# lcd.net
KiCad netlist of a schematic drawn in EAGLE
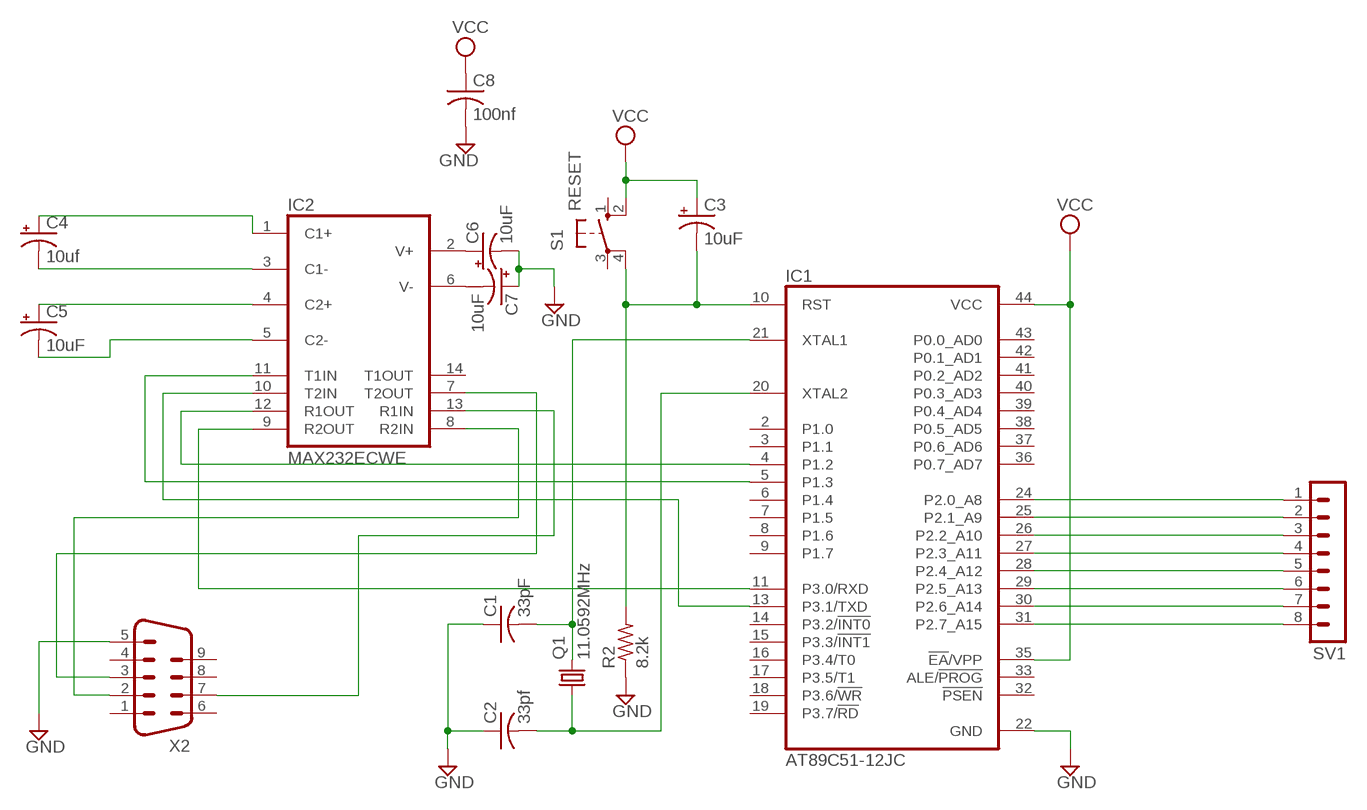
[diagram p0: schematic, sheet 1]

(export (version "E")
  (design (tool "Eeschema 10.0.6"))
  (components
    (comp (ref "C1")
      (value "33pF")
      (footprint "eagle-import:C025-025X050")
      (libsource (lib "eagle-import") (part "C-US025-025X050"))
    )
    (comp (ref "C2")
      (value "33pf")
      (footprint "eagle-import:C025-025X050")
      (libsource (lib "eagle-import") (part "C-US025-025X050"))
    )
    (comp (ref "C3")
      (value "10uF")
      (footprint "eagle-import:E2,5-5")
      (libsource (lib "eagle-import") (part "CPOL-USE2.5-5"))
    )
    (comp (ref "C4")
      (value "10uf")
      (footprint "eagle-import:E2,5-5")
      (libsource (lib "eagle-import") (part "CPOL-USE2.5-5"))
    )
    (comp (ref "C5")
      (value "10uF")
      (footprint "eagle-import:E2,5-5")
      (libsource (lib "eagle-import") (part "CPOL-USE2.5-5"))
    )
    (comp (ref "C6")
      (value "10uF")
      (footprint "eagle-import:E2,5-5")
      (libsource (lib "eagle-import") (part "CPOL-USE2.5-5"))
    )
    (comp (ref "C7")
      (value "10uF")
      (footprint "eagle-import:E2,5-5")
      (libsource (lib "eagle-import") (part "CPOL-USE2.5-5"))
    )
    (comp (ref "C8")
      (value "100nf")
      (footprint "eagle-import:C025-025X050")
      (libsource (lib "eagle-import") (part "C-US025-025X050"))
    )
    (comp (ref "IC1")
      (value "AT89C51-12JC")
      (footprint "eagle-import:PLCC44")
      (fields (field (name "MPN") "AT89C51ED2-SLSUM"))
      (libsource (lib "eagle-import") (part "AT89C51-JC12"))
    )
    (comp (ref "IC2")
      (value "MAX232ECWE")
      (footprint "eagle-import:SO16L")
      (fields (field (name "MF") "MAXIM") (field (name "MPN") "MAX232ECWE+"))
      (libsource (lib "eagle-import") (part "MAX232ECWE"))
    )
    (comp (ref "Q1")
      (value "11.0592MHz")
      (footprint "eagle-import:TC26H")
      (libsource (lib "eagle-import") (part "CRYSTALTC26H"))
    )
    (comp (ref "R2")
      (value "8.2k")
      (footprint "eagle-import:R2512")
      (libsource (lib "eagle-import") (part "R-US_R2512"))
    )
    (comp (ref "S1")
      (value "RESET")
      (footprint "eagle-import:B3F-10XX")
      (fields (field (name "MPN") "B3F-1000"))
      (libsource (lib "eagle-import") (part "10-XX"))
    )
    (comp (ref "SV1")
      (value "MA08-1W")
      (footprint "eagle-import:MA08-1W")
      (libsource (lib "eagle-import") (part "MA08-1W"))
    )
    (comp (ref "X2")
      (value "M09V")
      (footprint "eagle-import:M09V")
      (libsource (lib "eagle-import") (part "M09V"))
    )
  )
  (nets
    (net (code "1") (name "GND") (class "Default")
      (node (ref "C1") (pin "1") (pinfunction "1_1") (pintype "passive"))
      (node (ref "C2") (pin "1") (pinfunction "1_1") (pintype "passive"))
      (node (ref "C6") (pin "-") (pinfunction "-_-") (pintype "passive"))
      (node (ref "C7") (pin "+") (pinfunction "+_+") (pintype "passive"))
      (node (ref "C8") (pin "2") (pinfunction "2_2") (pintype "passive"))
      (node (ref "IC1") (pin "22") (pinfunction "GND_22") (pintype "power_in"))
      (node (ref "R2") (pin "1") (pinfunction "1_1") (pintype "passive"))
      (node (ref "X2") (pin "5") (pinfunction "5_5") (pintype "passive"))
    )
    (net (code "2") (name "Net-(IC1-P1.2)") (class "Default")
      (node (ref "IC1") (pin "4") (pinfunction "P1.2_4") (pintype "bidirectional"))
      (node (ref "IC2") (pin "12") (pinfunction "R1OUT_12") (pintype "output"))
    )
    (net (code "3") (name "Net-(IC1-P1.3)") (class "Default")
      (node (ref "IC1") (pin "5") (pinfunction "P1.3_5") (pintype "bidirectional"))
      (node (ref "IC2") (pin "11") (pinfunction "T1IN_11") (pintype "input"))
    )
    (net (code "4") (name "Net-(IC1-P2.0_A8)") (class "Default")
      (node (ref "IC1") (pin "24") (pinfunction "P2.0_A8_24") (pintype "bidirectional"))
      (node (ref "SV1") (pin "1") (pinfunction "1_1") (pintype "passive"))
    )
    (net (code "5") (name "Net-(IC1-P2.1_A9)") (class "Default")
      (node (ref "IC1") (pin "25") (pinfunction "P2.1_A9_25") (pintype "bidirectional"))
      (node (ref "SV1") (pin "2") (pinfunction "2_2") (pintype "passive"))
    )
    (net (code "6") (name "Net-(IC1-P2.2_A10)") (class "Default")
      (node (ref "IC1") (pin "26") (pinfunction "P2.2_A10_26") (pintype "bidirectional"))
      (node (ref "SV1") (pin "3") (pinfunction "3_3") (pintype "passive"))
    )
    (net (code "7") (name "Net-(IC1-P2.3_A11)") (class "Default")
      (node (ref "IC1") (pin "27") (pinfunction "P2.3_A11_27") (pintype "bidirectional"))
      (node (ref "SV1") (pin "4") (pinfunction "4_4") (pintype "passive"))
    )
    (net (code "8") (name "Net-(IC1-P2.4_A12)") (class "Default")
      (node (ref "IC1") (pin "28") (pinfunction "P2.4_A12_28") (pintype "bidirectional"))
      (node (ref "SV1") (pin "5") (pinfunction "5_5") (pintype "passive"))
    )
    (net (code "9") (name "Net-(IC1-P2.5_A13)") (class "Default")
      (node (ref "IC1") (pin "29") (pinfunction "P2.5_A13_29") (pintype "bidirectional"))
      (node (ref "SV1") (pin "6") (pinfunction "6_6") (pintype "passive"))
    )
    (net (code "10") (name "Net-(IC1-P2.6_A14)") (class "Default")
      (node (ref "IC1") (pin "30") (pinfunction "P2.6_A14_30") (pintype "bidirectional"))
      (node (ref "SV1") (pin "7") (pinfunction "7_7") (pintype "passive"))
    )
    (net (code "11") (name "Net-(IC1-P2.7_A15)") (class "Default")
      (node (ref "IC1") (pin "31") (pinfunction "P2.7_A15_31") (pintype "bidirectional"))
      (node (ref "SV1") (pin "8") (pinfunction "8_8") (pintype "passive"))
    )
    (net (code "12") (name "Net-(IC1-P3.0{slash}RXD)") (class "Default")
      (node (ref "IC1") (pin "11") (pinfunction "P3.0/RXD_11") (pintype "bidirectional"))
      (node (ref "IC2") (pin "9") (pinfunction "R2OUT_9") (pintype "output"))
    )
    (net (code "13") (name "Net-(IC1-P3.1{slash}TXD)") (class "Default")
      (node (ref "IC1") (pin "13") (pinfunction "P3.1/TXD_13") (pintype "bidirectional"))
      (node (ref "IC2") (pin "10") (pinfunction "T2IN_10") (pintype "input"))
    )
    (net (code "14") (name "Net-(IC1-RST)") (class "Default")
      (node (ref "C3") (pin "-") (pinfunction "-_-") (pintype "passive"))
      (node (ref "IC1") (pin "10") (pinfunction "RST_10") (pintype "input"))
      (node (ref "R2") (pin "2") (pinfunction "2_2") (pintype "passive"))
      (node (ref "S1") (pin "4") (pinfunction "P1_4") (pintype "passive"))
    )
    (net (code "15") (name "Net-(IC1-XTAL1)") (class "Default")
      (node (ref "C1") (pin "2") (pinfunction "2_2") (pintype "passive"))
      (node (ref "IC1") (pin "21") (pinfunction "XTAL1_21") (pintype "input"))
      (node (ref "Q1") (pin "2") (pinfunction "2_2") (pintype "passive"))
    )
    (net (code "16") (name "Net-(IC1-XTAL2)") (class "Default")
      (node (ref "C2") (pin "2") (pinfunction "2_2") (pintype "passive"))
      (node (ref "IC1") (pin "20") (pinfunction "XTAL2_20") (pintype "input"))
      (node (ref "Q1") (pin "1") (pinfunction "1_1") (pintype "passive"))
    )
    (net (code "17") (name "Net-(IC2A-C1+)") (class "Default")
      (node (ref "C4") (pin "+") (pinfunction "+_+") (pintype "passive"))
      (node (ref "IC2") (pin "1") (pinfunction "C1+_1") (pintype "bidirectional"))
    )
    (net (code "18") (name "Net-(IC2A-C1-)") (class "Default")
      (node (ref "C4") (pin "-") (pinfunction "-_-") (pintype "passive"))
      (node (ref "IC2") (pin "3") (pinfunction "C1-_3") (pintype "bidirectional"))
    )
    (net (code "19") (name "Net-(IC2A-C2+)") (class "Default")
      (node (ref "C5") (pin "+") (pinfunction "+_+") (pintype "passive"))
      (node (ref "IC2") (pin "4") (pinfunction "C2+_4") (pintype "bidirectional"))
    )
    (net (code "20") (name "Net-(IC2A-C2-)") (class "Default")
      (node (ref "C5") (pin "-") (pinfunction "-_-") (pintype "passive"))
      (node (ref "IC2") (pin "5") (pinfunction "C2-_5") (pintype "bidirectional"))
    )
    (net (code "21") (name "Net-(IC2A-R1IN)") (class "Default")
      (node (ref "IC2") (pin "13") (pinfunction "R1IN_13") (pintype "input"))
      (node (ref "X2") (pin "7") (pinfunction "7_7") (pintype "passive"))
    )
    (net (code "22") (name "Net-(IC2A-R2IN)") (class "Default")
      (node (ref "IC2") (pin "8") (pinfunction "R2IN_8") (pintype "input"))
      (node (ref "X2") (pin "2") (pinfunction "2_2") (pintype "passive"))
    )
    (net (code "23") (name "Net-(IC2A-T2OUT)") (class "Default")
      (node (ref "IC2") (pin "7") (pinfunction "T2OUT_7") (pintype "output"))
      (node (ref "X2") (pin "3") (pinfunction "3_3") (pintype "passive"))
    )
    (net (code "24") (name "Net-(IC2A-V+)") (class "Default")
      (node (ref "C6") (pin "+") (pinfunction "+_+") (pintype "passive"))
      (node (ref "IC2") (pin "2") (pinfunction "V+_2") (pintype "bidirectional"))
    )
    (net (code "25") (name "Net-(IC2A-V-)") (class "Default")
      (node (ref "C7") (pin "-") (pinfunction "-_-") (pintype "passive"))
      (node (ref "IC2") (pin "6") (pinfunction "V-_6") (pintype "bidirectional"))
    )
    (net (code "26") (name "VCC") (class "Default")
      (node (ref "C3") (pin "+") (pinfunction "+_+") (pintype "passive"))
      (node (ref "C8") (pin "1") (pinfunction "1_1") (pintype "passive"))
      (node (ref "IC1") (pin "35") (pinfunction "~{EA}/VPP_35") (pintype "input"))
      (node (ref "IC1") (pin "44") (pinfunction "VCC_44") (pintype "power_in"))
      (node (ref "S1") (pin "2") (pinfunction "S1_2") (pintype "passive"))
    )
    (net (code "27") (name "unconnected-(IC1-ALE{slash}~{PROG}-Pad33)") (class "Default")
      (node (ref "IC1") (pin "33") (pinfunction "ALE/~{PROG}_33") (pintype "output"))
    )
    (net (code "28") (name "unconnected-(IC1-P0.0_AD0-Pad43)") (class "Default")
      (node (ref "IC1") (pin "43") (pinfunction "P0.0_AD0_43") (pintype "bidirectional"))
    )
    (net (code "29") (name "unconnected-(IC1-P0.1_AD1-Pad42)") (class "Default")
      (node (ref "IC1") (pin "42") (pinfunction "P0.1_AD1_42") (pintype "bidirectional"))
    )
    (net (code "30") (name "unconnected-(IC1-P0.2_AD2-Pad41)") (class "Default")
      (node (ref "IC1") (pin "41") (pinfunction "P0.2_AD2_41") (pintype "bidirectional"))
    )
    (net (code "31") (name "unconnected-(IC1-P0.3_AD3-Pad40)") (class "Default")
      (node (ref "IC1") (pin "40") (pinfunction "P0.3_AD3_40") (pintype "bidirectional"))
    )
    (net (code "32") (name "unconnected-(IC1-P0.4_AD4-Pad39)") (class "Default")
      (node (ref "IC1") (pin "39") (pinfunction "P0.4_AD4_39") (pintype "bidirectional"))
    )
    (net (code "33") (name "unconnected-(IC1-P0.5_AD5-Pad38)") (class "Default")
      (node (ref "IC1") (pin "38") (pinfunction "P0.5_AD5_38") (pintype "bidirectional"))
    )
    (net (code "34") (name "unconnected-(IC1-P0.6_AD6-Pad37)") (class "Default")
      (node (ref "IC1") (pin "37") (pinfunction "P0.6_AD6_37") (pintype "bidirectional"))
    )
    (net (code "35") (name "unconnected-(IC1-P0.7_AD7-Pad36)") (class "Default")
      (node (ref "IC1") (pin "36") (pinfunction "P0.7_AD7_36") (pintype "bidirectional"))
    )
    (net (code "36") (name "unconnected-(IC1-P1.0-Pad2)") (class "Default")
      (node (ref "IC1") (pin "2") (pinfunction "P1.0_2") (pintype "bidirectional"))
    )
    (net (code "37") (name "unconnected-(IC1-P1.1-Pad3)") (class "Default")
      (node (ref "IC1") (pin "3") (pinfunction "P1.1_3") (pintype "bidirectional"))
    )
    (net (code "38") (name "unconnected-(IC1-P1.4-Pad6)") (class "Default")
      (node (ref "IC1") (pin "6") (pinfunction "P1.4_6") (pintype "bidirectional"))
    )
    (net (code "39") (name "unconnected-(IC1-P1.5-Pad7)") (class "Default")
      (node (ref "IC1") (pin "7") (pinfunction "P1.5_7") (pintype "bidirectional"))
    )
    (net (code "40") (name "unconnected-(IC1-P1.6-Pad8)") (class "Default")
      (node (ref "IC1") (pin "8") (pinfunction "P1.6_8") (pintype "bidirectional"))
    )
    (net (code "41") (name "unconnected-(IC1-P1.7-Pad9)") (class "Default")
      (node (ref "IC1") (pin "9") (pinfunction "P1.7_9") (pintype "bidirectional"))
    )
    (net (code "42") (name "unconnected-(IC1-P3.2{slash}~{INT0}-Pad14)") (class "Default")
      (node (ref "IC1") (pin "14") (pinfunction "P3.2/~{INT0}_14") (pintype "bidirectional"))
    )
    (net (code "43") (name "unconnected-(IC1-P3.3{slash}~{INT1}-Pad15)") (class "Default")
      (node (ref "IC1") (pin "15") (pinfunction "P3.3/~{INT1}_15") (pintype "bidirectional"))
    )
    (net (code "44") (name "unconnected-(IC1-P3.4{slash}T0-Pad16)") (class "Default")
      (node (ref "IC1") (pin "16") (pinfunction "P3.4/T0_16") (pintype "bidirectional"))
    )
    (net (code "45") (name "unconnected-(IC1-P3.5{slash}T1-Pad17)") (class "Default")
      (node (ref "IC1") (pin "17") (pinfunction "P3.5/T1_17") (pintype "bidirectional"))
    )
    (net (code "46") (name "unconnected-(IC1-P3.6{slash}~{WR}-Pad18)") (class "Default")
      (node (ref "IC1") (pin "18") (pinfunction "P3.6/~{WR}_18") (pintype "bidirectional"))
    )
    (net (code "47") (name "unconnected-(IC1-P3.7{slash}~{RD}-Pad19)") (class "Default")
      (node (ref "IC1") (pin "19") (pinfunction "P3.7/~{RD}_19") (pintype "bidirectional"))
    )
    (net (code "48") (name "unconnected-(IC1-~{PSEN}-Pad32)") (class "Default")
      (node (ref "IC1") (pin "32") (pinfunction "~{PSEN}_32") (pintype "output"))
    )
    (net (code "49") (name "unconnected-(IC2A-T1OUT-Pad14)") (class "Default")
      (node (ref "IC2") (pin "14") (pinfunction "T1OUT_14") (pintype "output"))
    )
    (net (code "50") (name "unconnected-(S1-P-Pad3)") (class "Default")
      (node (ref "S1") (pin "3") (pinfunction "P_3") (pintype "passive"))
    )
    (net (code "51") (name "unconnected-(S1-S-Pad1)") (class "Default")
      (node (ref "S1") (pin "1") (pinfunction "S_1") (pintype "passive"))
    )
    (net (code "52") (name "unconnected-(X2-Pad1)") (class "Default")
      (node (ref "X2") (pin "1") (pinfunction "1_1") (pintype "passive"))
    )
    (net (code "53") (name "unconnected-(X2-Pad4)") (class "Default")
      (node (ref "X2") (pin "4") (pinfunction "4_4") (pintype "passive"))
    )
    (net (code "54") (name "unconnected-(X2-Pad6)") (class "Default")
      (node (ref "X2") (pin "6") (pinfunction "6_6") (pintype "passive"))
    )
    (net (code "55") (name "unconnected-(X2-Pad8)") (class "Default")
      (node (ref "X2") (pin "8") (pinfunction "8_8") (pintype "passive"))
    )
    (net (code "56") (name "unconnected-(X2-Pad9)") (class "Default")
      (node (ref "X2") (pin "9") (pinfunction "9_9") (pintype "passive"))
    )
  )
)
